# DSUB_SCSI.net
KiCad netlist of a schematic drawn in EAGLE
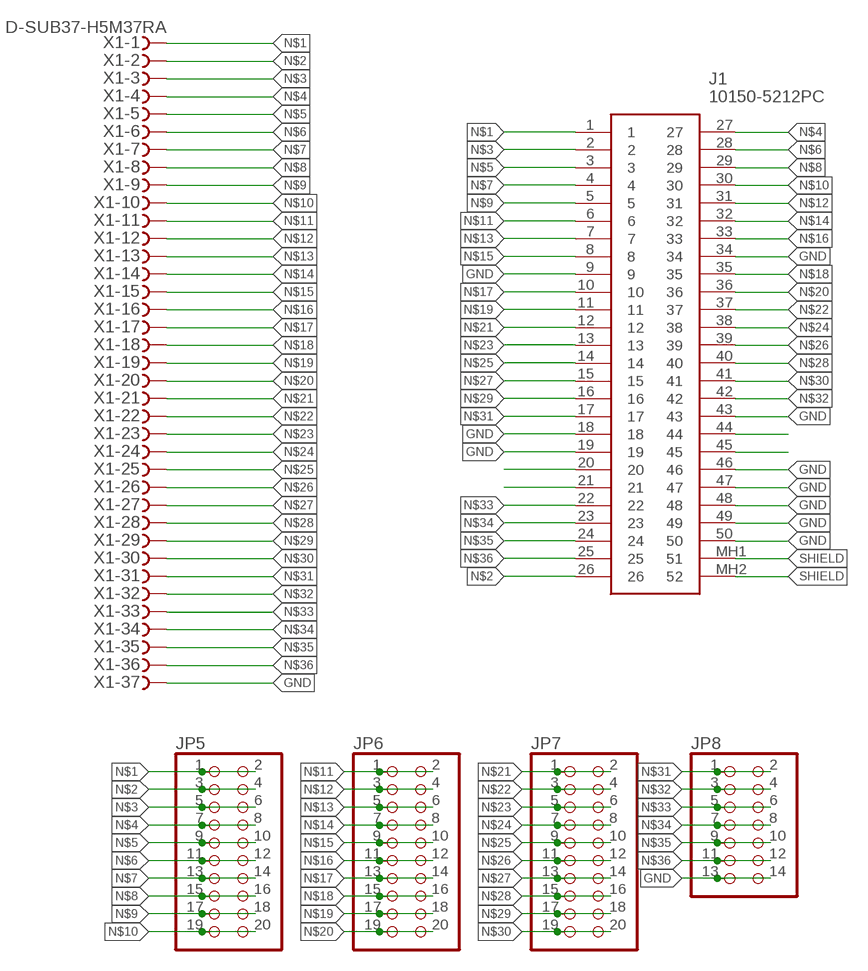
[diagram p0: schematic, sheet 1]

(export (version "E")
  (design (tool "Eeschema 10.0.6"))
  (components
    (comp (ref "J1")
      (value "10150-5212PC")
      (footprint "eagle-import:101505212PC")
      (fields (field (name "MOUSER_PART_NUMBER") "517-10150-5212PC"))
      (libsource (lib "eagle-import") (part "10150-5212PC"))
    )
    (comp (ref "JP5")
      (value "PINHD-2X10")
      (footprint "eagle-import:2X10")
      (libsource (lib "eagle-import") (part "PINHD-2X10"))
    )
    (comp (ref "JP6")
      (value "PINHD-2X10")
      (footprint "eagle-import:2X10")
      (libsource (lib "eagle-import") (part "PINHD-2X10"))
    )
    (comp (ref "JP7")
      (value "PINHD-2X10")
      (footprint "eagle-import:2X10")
      (libsource (lib "eagle-import") (part "PINHD-2X10"))
    )
    (comp (ref "JP8")
      (value "PINHD-2X7")
      (footprint "eagle-import:2X07")
      (libsource (lib "eagle-import") (part "PINHD-2X7"))
    )
    (comp (ref "X1")
      (value "D-SUB37-H5M37RA")
      (footprint "eagle-import:H5M37RA")
      (fields (field (name "MPN") "H5M37RA29CS"))
      (libsource (lib "eagle-import") (part "D-SUB37-H5M37RA"))
    )
  )
  (nets
    (net (code "1") (name "GND") (class "Default")
      (node (ref "J1") (pin "18") (pinfunction "18_18") (pintype "bidirectional"))
      (node (ref "J1") (pin "19") (pinfunction "19_19") (pintype "bidirectional"))
      (node (ref "J1") (pin "34") (pinfunction "34_34") (pintype "bidirectional"))
      (node (ref "J1") (pin "43") (pinfunction "43_43") (pintype "bidirectional"))
      (node (ref "J1") (pin "46") (pinfunction "46_46") (pintype "bidirectional"))
      (node (ref "J1") (pin "47") (pinfunction "47_47") (pintype "bidirectional"))
      (node (ref "J1") (pin "48") (pinfunction "48_48") (pintype "bidirectional"))
      (node (ref "J1") (pin "49") (pinfunction "49_49") (pintype "bidirectional"))
      (node (ref "J1") (pin "50") (pinfunction "50_50") (pintype "bidirectional"))
      (node (ref "J1") (pin "9") (pinfunction "9_9") (pintype "bidirectional"))
      (node (ref "JP8") (pin "13") (pinfunction "13_13") (pintype "passive"))
      (node (ref "JP8") (pin "14") (pinfunction "14_14") (pintype "passive"))
      (node (ref "X1") (pin "37") (pinfunction "F_37") (pintype "passive"))
    )
    (net (code "2") (name "N$1") (class "Default")
      (node (ref "J1") (pin "1") (pinfunction "1_1") (pintype "bidirectional"))
      (node (ref "JP5") (pin "1") (pinfunction "1_1") (pintype "passive"))
      (node (ref "JP5") (pin "2") (pinfunction "2_2") (pintype "passive"))
      (node (ref "X1") (pin "1") (pinfunction "F_1") (pintype "passive"))
    )
    (net (code "3") (name "N$2") (class "Default")
      (node (ref "J1") (pin "26") (pinfunction "26_26") (pintype "bidirectional"))
      (node (ref "JP5") (pin "3") (pinfunction "3_3") (pintype "passive"))
      (node (ref "JP5") (pin "4") (pinfunction "4_4") (pintype "passive"))
      (node (ref "X1") (pin "2") (pinfunction "F_2") (pintype "passive"))
    )
    (net (code "4") (name "N$3") (class "Default")
      (node (ref "J1") (pin "2") (pinfunction "2_2") (pintype "bidirectional"))
      (node (ref "JP5") (pin "5") (pinfunction "5_5") (pintype "passive"))
      (node (ref "JP5") (pin "6") (pinfunction "6_6") (pintype "passive"))
      (node (ref "X1") (pin "3") (pinfunction "F_3") (pintype "passive"))
    )
    (net (code "5") (name "N$4") (class "Default")
      (node (ref "J1") (pin "27") (pinfunction "27_27") (pintype "bidirectional"))
      (node (ref "JP5") (pin "7") (pinfunction "7_7") (pintype "passive"))
      (node (ref "JP5") (pin "8") (pinfunction "8_8") (pintype "passive"))
      (node (ref "X1") (pin "4") (pinfunction "F_4") (pintype "passive"))
    )
    (net (code "6") (name "N$5") (class "Default")
      (node (ref "J1") (pin "3") (pinfunction "3_3") (pintype "bidirectional"))
      (node (ref "JP5") (pin "10") (pinfunction "10_10") (pintype "passive"))
      (node (ref "JP5") (pin "9") (pinfunction "9_9") (pintype "passive"))
      (node (ref "X1") (pin "5") (pinfunction "F_5") (pintype "passive"))
    )
    (net (code "7") (name "N$6") (class "Default")
      (node (ref "J1") (pin "28") (pinfunction "28_28") (pintype "bidirectional"))
      (node (ref "JP5") (pin "11") (pinfunction "11_11") (pintype "passive"))
      (node (ref "JP5") (pin "12") (pinfunction "12_12") (pintype "passive"))
      (node (ref "X1") (pin "6") (pinfunction "F_6") (pintype "passive"))
    )
    (net (code "8") (name "N$7") (class "Default")
      (node (ref "J1") (pin "4") (pinfunction "4_4") (pintype "bidirectional"))
      (node (ref "JP5") (pin "13") (pinfunction "13_13") (pintype "passive"))
      (node (ref "JP5") (pin "14") (pinfunction "14_14") (pintype "passive"))
      (node (ref "X1") (pin "7") (pinfunction "F_7") (pintype "passive"))
    )
    (net (code "9") (name "N$8") (class "Default")
      (node (ref "J1") (pin "29") (pinfunction "29_29") (pintype "bidirectional"))
      (node (ref "JP5") (pin "15") (pinfunction "15_15") (pintype "passive"))
      (node (ref "JP5") (pin "16") (pinfunction "16_16") (pintype "passive"))
      (node (ref "X1") (pin "8") (pinfunction "F_8") (pintype "passive"))
    )
    (net (code "10") (name "N$9") (class "Default")
      (node (ref "J1") (pin "5") (pinfunction "5_5") (pintype "bidirectional"))
      (node (ref "JP5") (pin "17") (pinfunction "17_17") (pintype "passive"))
      (node (ref "JP5") (pin "18") (pinfunction "18_18") (pintype "passive"))
      (node (ref "X1") (pin "9") (pinfunction "F_9") (pintype "passive"))
    )
    (net (code "11") (name "N$10") (class "Default")
      (node (ref "J1") (pin "30") (pinfunction "30_30") (pintype "bidirectional"))
      (node (ref "JP5") (pin "19") (pinfunction "19_19") (pintype "passive"))
      (node (ref "JP5") (pin "20") (pinfunction "20_20") (pintype "passive"))
      (node (ref "X1") (pin "10") (pinfunction "F_10") (pintype "passive"))
    )
    (net (code "12") (name "N$11") (class "Default")
      (node (ref "J1") (pin "6") (pinfunction "6_6") (pintype "bidirectional"))
      (node (ref "JP6") (pin "1") (pinfunction "1_1") (pintype "passive"))
      (node (ref "JP6") (pin "2") (pinfunction "2_2") (pintype "passive"))
      (node (ref "X1") (pin "11") (pinfunction "F_11") (pintype "passive"))
    )
    (net (code "13") (name "N$12") (class "Default")
      (node (ref "J1") (pin "31") (pinfunction "31_31") (pintype "bidirectional"))
      (node (ref "JP6") (pin "3") (pinfunction "3_3") (pintype "passive"))
      (node (ref "JP6") (pin "4") (pinfunction "4_4") (pintype "passive"))
      (node (ref "X1") (pin "12") (pinfunction "F_12") (pintype "passive"))
    )
    (net (code "14") (name "N$13") (class "Default")
      (node (ref "J1") (pin "7") (pinfunction "7_7") (pintype "bidirectional"))
      (node (ref "JP6") (pin "5") (pinfunction "5_5") (pintype "passive"))
      (node (ref "JP6") (pin "6") (pinfunction "6_6") (pintype "passive"))
      (node (ref "X1") (pin "13") (pinfunction "F_13") (pintype "passive"))
    )
    (net (code "15") (name "N$14") (class "Default")
      (node (ref "J1") (pin "32") (pinfunction "32_32") (pintype "bidirectional"))
      (node (ref "JP6") (pin "7") (pinfunction "7_7") (pintype "passive"))
      (node (ref "JP6") (pin "8") (pinfunction "8_8") (pintype "passive"))
      (node (ref "X1") (pin "14") (pinfunction "F_14") (pintype "passive"))
    )
    (net (code "16") (name "N$15") (class "Default")
      (node (ref "J1") (pin "8") (pinfunction "8_8") (pintype "bidirectional"))
      (node (ref "JP6") (pin "10") (pinfunction "10_10") (pintype "passive"))
      (node (ref "JP6") (pin "9") (pinfunction "9_9") (pintype "passive"))
      (node (ref "X1") (pin "15") (pinfunction "F_15") (pintype "passive"))
    )
    (net (code "17") (name "N$16") (class "Default")
      (node (ref "J1") (pin "33") (pinfunction "33_33") (pintype "bidirectional"))
      (node (ref "JP6") (pin "11") (pinfunction "11_11") (pintype "passive"))
      (node (ref "JP6") (pin "12") (pinfunction "12_12") (pintype "passive"))
      (node (ref "X1") (pin "16") (pinfunction "F_16") (pintype "passive"))
    )
    (net (code "18") (name "N$17") (class "Default")
      (node (ref "J1") (pin "10") (pinfunction "10_10") (pintype "bidirectional"))
      (node (ref "JP6") (pin "13") (pinfunction "13_13") (pintype "passive"))
      (node (ref "JP6") (pin "14") (pinfunction "14_14") (pintype "passive"))
      (node (ref "X1") (pin "17") (pinfunction "F_17") (pintype "passive"))
    )
    (net (code "19") (name "N$18") (class "Default")
      (node (ref "J1") (pin "35") (pinfunction "35_35") (pintype "bidirectional"))
      (node (ref "JP6") (pin "15") (pinfunction "15_15") (pintype "passive"))
      (node (ref "JP6") (pin "16") (pinfunction "16_16") (pintype "passive"))
      (node (ref "X1") (pin "18") (pinfunction "F_18") (pintype "passive"))
    )
    (net (code "20") (name "N$19") (class "Default")
      (node (ref "J1") (pin "11") (pinfunction "11_11") (pintype "bidirectional"))
      (node (ref "JP6") (pin "17") (pinfunction "17_17") (pintype "passive"))
      (node (ref "JP6") (pin "18") (pinfunction "18_18") (pintype "passive"))
      (node (ref "X1") (pin "19") (pinfunction "F_19") (pintype "passive"))
    )
    (net (code "21") (name "N$20") (class "Default")
      (node (ref "J1") (pin "36") (pinfunction "36_36") (pintype "bidirectional"))
      (node (ref "JP6") (pin "19") (pinfunction "19_19") (pintype "passive"))
      (node (ref "JP6") (pin "20") (pinfunction "20_20") (pintype "passive"))
      (node (ref "X1") (pin "20") (pinfunction "F_20") (pintype "passive"))
    )
    (net (code "22") (name "N$21") (class "Default")
      (node (ref "J1") (pin "12") (pinfunction "12_12") (pintype "bidirectional"))
      (node (ref "JP7") (pin "1") (pinfunction "1_1") (pintype "passive"))
      (node (ref "JP7") (pin "2") (pinfunction "2_2") (pintype "passive"))
      (node (ref "X1") (pin "21") (pinfunction "F_21") (pintype "passive"))
    )
    (net (code "23") (name "N$22") (class "Default")
      (node (ref "J1") (pin "37") (pinfunction "37_37") (pintype "bidirectional"))
      (node (ref "JP7") (pin "3") (pinfunction "3_3") (pintype "passive"))
      (node (ref "JP7") (pin "4") (pinfunction "4_4") (pintype "passive"))
      (node (ref "X1") (pin "22") (pinfunction "F_22") (pintype "passive"))
    )
    (net (code "24") (name "N$23") (class "Default")
      (node (ref "J1") (pin "13") (pinfunction "13_13") (pintype "bidirectional"))
      (node (ref "JP7") (pin "5") (pinfunction "5_5") (pintype "passive"))
      (node (ref "JP7") (pin "6") (pinfunction "6_6") (pintype "passive"))
      (node (ref "X1") (pin "23") (pinfunction "F_23") (pintype "passive"))
    )
    (net (code "25") (name "N$24") (class "Default")
      (node (ref "J1") (pin "38") (pinfunction "38_38") (pintype "bidirectional"))
      (node (ref "JP7") (pin "7") (pinfunction "7_7") (pintype "passive"))
      (node (ref "JP7") (pin "8") (pinfunction "8_8") (pintype "passive"))
      (node (ref "X1") (pin "24") (pinfunction "F_24") (pintype "passive"))
    )
    (net (code "26") (name "N$25") (class "Default")
      (node (ref "J1") (pin "14") (pinfunction "14_14") (pintype "bidirectional"))
      (node (ref "JP7") (pin "10") (pinfunction "10_10") (pintype "passive"))
      (node (ref "JP7") (pin "9") (pinfunction "9_9") (pintype "passive"))
      (node (ref "X1") (pin "25") (pinfunction "F_25") (pintype "passive"))
    )
    (net (code "27") (name "N$26") (class "Default")
      (node (ref "J1") (pin "39") (pinfunction "39_39") (pintype "bidirectional"))
      (node (ref "JP7") (pin "11") (pinfunction "11_11") (pintype "passive"))
      (node (ref "JP7") (pin "12") (pinfunction "12_12") (pintype "passive"))
      (node (ref "X1") (pin "26") (pinfunction "F_26") (pintype "passive"))
    )
    (net (code "28") (name "N$27") (class "Default")
      (node (ref "J1") (pin "15") (pinfunction "15_15") (pintype "bidirectional"))
      (node (ref "JP7") (pin "13") (pinfunction "13_13") (pintype "passive"))
      (node (ref "JP7") (pin "14") (pinfunction "14_14") (pintype "passive"))
      (node (ref "X1") (pin "27") (pinfunction "F_27") (pintype "passive"))
    )
    (net (code "29") (name "N$28") (class "Default")
      (node (ref "J1") (pin "40") (pinfunction "40_40") (pintype "bidirectional"))
      (node (ref "JP7") (pin "15") (pinfunction "15_15") (pintype "passive"))
      (node (ref "JP7") (pin "16") (pinfunction "16_16") (pintype "passive"))
      (node (ref "X1") (pin "28") (pinfunction "F_28") (pintype "passive"))
    )
    (net (code "30") (name "N$29") (class "Default")
      (node (ref "J1") (pin "16") (pinfunction "16_16") (pintype "bidirectional"))
      (node (ref "JP7") (pin "17") (pinfunction "17_17") (pintype "passive"))
      (node (ref "JP7") (pin "18") (pinfunction "18_18") (pintype "passive"))
      (node (ref "X1") (pin "29") (pinfunction "F_29") (pintype "passive"))
    )
    (net (code "31") (name "N$30") (class "Default")
      (node (ref "J1") (pin "41") (pinfunction "41_41") (pintype "bidirectional"))
      (node (ref "JP7") (pin "19") (pinfunction "19_19") (pintype "passive"))
      (node (ref "JP7") (pin "20") (pinfunction "20_20") (pintype "passive"))
      (node (ref "X1") (pin "30") (pinfunction "F_30") (pintype "passive"))
    )
    (net (code "32") (name "N$31") (class "Default")
      (node (ref "J1") (pin "17") (pinfunction "17_17") (pintype "bidirectional"))
      (node (ref "JP8") (pin "1") (pinfunction "1_1") (pintype "passive"))
      (node (ref "JP8") (pin "2") (pinfunction "2_2") (pintype "passive"))
      (node (ref "X1") (pin "31") (pinfunction "F_31") (pintype "passive"))
    )
    (net (code "33") (name "N$32") (class "Default")
      (node (ref "J1") (pin "42") (pinfunction "42_42") (pintype "bidirectional"))
      (node (ref "JP8") (pin "3") (pinfunction "3_3") (pintype "passive"))
      (node (ref "JP8") (pin "4") (pinfunction "4_4") (pintype "passive"))
      (node (ref "X1") (pin "32") (pinfunction "F_32") (pintype "passive"))
    )
    (net (code "34") (name "N$33") (class "Default")
      (node (ref "J1") (pin "22") (pinfunction "22_22") (pintype "bidirectional"))
      (node (ref "JP8") (pin "5") (pinfunction "5_5") (pintype "passive"))
      (node (ref "JP8") (pin "6") (pinfunction "6_6") (pintype "passive"))
      (node (ref "X1") (pin "33") (pinfunction "F_33") (pintype "passive"))
    )
    (net (code "35") (name "N$34") (class "Default")
      (node (ref "J1") (pin "23") (pinfunction "23_23") (pintype "bidirectional"))
      (node (ref "JP8") (pin "7") (pinfunction "7_7") (pintype "passive"))
      (node (ref "JP8") (pin "8") (pinfunction "8_8") (pintype "passive"))
      (node (ref "X1") (pin "34") (pinfunction "F_34") (pintype "passive"))
    )
    (net (code "36") (name "N$35") (class "Default")
      (node (ref "J1") (pin "24") (pinfunction "24_24") (pintype "bidirectional"))
      (node (ref "JP8") (pin "10") (pinfunction "10_10") (pintype "passive"))
      (node (ref "JP8") (pin "9") (pinfunction "9_9") (pintype "passive"))
      (node (ref "X1") (pin "35") (pinfunction "F_35") (pintype "passive"))
    )
    (net (code "37") (name "N$36") (class "Default")
      (node (ref "J1") (pin "25") (pinfunction "25_25") (pintype "bidirectional"))
      (node (ref "JP8") (pin "11") (pinfunction "11_11") (pintype "passive"))
      (node (ref "JP8") (pin "12") (pinfunction "12_12") (pintype "passive"))
      (node (ref "X1") (pin "36") (pinfunction "F_36") (pintype "passive"))
    )
    (net (code "38") (name "SHIELD") (class "Default")
      (node (ref "J1") (pin "MH1") (pinfunction "51_MH1") (pintype "bidirectional"))
      (node (ref "J1") (pin "MH2") (pinfunction "52_MH2") (pintype "bidirectional"))
    )
    (net (code "39") (name "unconnected-(J1-Pad20)") (class "Default")
      (node (ref "J1") (pin "20") (pinfunction "20_20") (pintype "bidirectional"))
    )
    (net (code "40") (name "unconnected-(J1-Pad21)") (class "Default")
      (node (ref "J1") (pin "21") (pinfunction "21_21") (pintype "bidirectional"))
    )
    (net (code "41") (name "unconnected-(J1-Pad44)") (class "Default")
      (node (ref "J1") (pin "44") (pinfunction "44_44") (pintype "bidirectional"))
    )
    (net (code "42") (name "unconnected-(J1-Pad45)") (class "Default")
      (node (ref "J1") (pin "45") (pinfunction "45_45") (pintype "bidirectional"))
    )
  )
)
